# Lamp.net
KiCad netlist of a schematic drawn in EAGLE
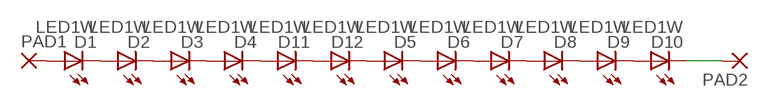
[diagram p0: schematic, sheet 1]

(export (version "E")
  (design (tool "Eeschema 10.0.6"))
  (components
    (comp (ref "D1")
      (value "LED1W")
      (footprint "eagle-import:LED-1W")
      (libsource (lib "eagle-import") (part "LED1W"))
    )
    (comp (ref "D2")
      (value "LED1W")
      (footprint "eagle-import:LED-1W")
      (libsource (lib "eagle-import") (part "LED1W"))
    )
    (comp (ref "D3")
      (value "LED1W")
      (footprint "eagle-import:LED-1W")
      (libsource (lib "eagle-import") (part "LED1W"))
    )
    (comp (ref "D4")
      (value "LED1W")
      (footprint "eagle-import:LED-1W")
      (libsource (lib "eagle-import") (part "LED1W"))
    )
    (comp (ref "D5")
      (value "LED1W")
      (footprint "eagle-import:LED-1W")
      (libsource (lib "eagle-import") (part "LED1W"))
    )
    (comp (ref "D6")
      (value "LED1W")
      (footprint "eagle-import:LED-1W")
      (libsource (lib "eagle-import") (part "LED1W"))
    )
    (comp (ref "D7")
      (value "LED1W")
      (footprint "eagle-import:LED-1W")
      (libsource (lib "eagle-import") (part "LED1W"))
    )
    (comp (ref "D8")
      (value "LED1W")
      (footprint "eagle-import:LED-1W")
      (libsource (lib "eagle-import") (part "LED1W"))
    )
    (comp (ref "D9")
      (value "LED1W")
      (footprint "eagle-import:LED-1W")
      (libsource (lib "eagle-import") (part "LED1W"))
    )
    (comp (ref "D10")
      (value "LED1W")
      (footprint "eagle-import:LED-1W")
      (libsource (lib "eagle-import") (part "LED1W"))
    )
    (comp (ref "D11")
      (value "LED1W")
      (footprint "eagle-import:LED-1W")
      (libsource (lib "eagle-import") (part "LED1W"))
    )
    (comp (ref "D12")
      (value "LED1W")
      (footprint "eagle-import:LED-1W")
      (libsource (lib "eagle-import") (part "LED1W"))
    )
    (comp (ref "PAD1")
      (value "3,81/1,4")
      (footprint "eagle-import:3,81_1,4")
      (libsource (lib "eagle-import") (part "3,81/1,4"))
    )
    (comp (ref "PAD2")
      (value "3,81/1,4")
      (footprint "eagle-import:3,81_1,4")
      (libsource (lib "eagle-import") (part "3,81/1,4"))
    )
  )
  (nets
    (net (code "1") (name "Net-(D1-C)") (class "Default")
      (node (ref "D1") (pin "K") (pinfunction "C_K") (pintype "passive"))
      (node (ref "D2") (pin "A") (pinfunction "A_A") (pintype "passive"))
    )
    (net (code "2") (name "Net-(D2-C)") (class "Default")
      (node (ref "D2") (pin "K") (pinfunction "C_K") (pintype "passive"))
      (node (ref "D3") (pin "A") (pinfunction "A_A") (pintype "passive"))
    )
    (net (code "3") (name "Net-(D3-C)") (class "Default")
      (node (ref "D3") (pin "K") (pinfunction "C_K") (pintype "passive"))
      (node (ref "D4") (pin "A") (pinfunction "A_A") (pintype "passive"))
    )
    (net (code "4") (name "Net-(D4-C)") (class "Default")
      (node (ref "D11") (pin "A") (pinfunction "A_A") (pintype "passive"))
      (node (ref "D4") (pin "K") (pinfunction "C_K") (pintype "passive"))
    )
    (net (code "5") (name "Net-(D5-C)") (class "Default")
      (node (ref "D5") (pin "K") (pinfunction "C_K") (pintype "passive"))
      (node (ref "D6") (pin "A") (pinfunction "A_A") (pintype "passive"))
    )
    (net (code "6") (name "Net-(D6-C)") (class "Default")
      (node (ref "D6") (pin "K") (pinfunction "C_K") (pintype "passive"))
      (node (ref "D7") (pin "A") (pinfunction "A_A") (pintype "passive"))
    )
    (net (code "7") (name "Net-(D7-C)") (class "Default")
      (node (ref "D7") (pin "K") (pinfunction "C_K") (pintype "passive"))
      (node (ref "D8") (pin "A") (pinfunction "A_A") (pintype "passive"))
    )
    (net (code "8") (name "Net-(D8-C)") (class "Default")
      (node (ref "D8") (pin "K") (pinfunction "C_K") (pintype "passive"))
      (node (ref "D9") (pin "A") (pinfunction "A_A") (pintype "passive"))
    )
    (net (code "9") (name "Net-(D9-C)") (class "Default")
      (node (ref "D10") (pin "A") (pinfunction "A_A") (pintype "passive"))
      (node (ref "D9") (pin "K") (pinfunction "C_K") (pintype "passive"))
    )
    (net (code "10") (name "Net-(D10-C)") (class "Default")
      (node (ref "D10") (pin "K") (pinfunction "C_K") (pintype "passive"))
      (node (ref "PAD2") (pin "1") (pinfunction "P_1") (pintype "passive"))
    )
    (net (code "11") (name "Net-(D11-C)") (class "Default")
      (node (ref "D11") (pin "K") (pinfunction "C_K") (pintype "passive"))
      (node (ref "D12") (pin "A") (pinfunction "A_A") (pintype "passive"))
    )
    (net (code "12") (name "Net-(D12-C)") (class "Default")
      (node (ref "D12") (pin "K") (pinfunction "C_K") (pintype "passive"))
      (node (ref "D5") (pin "A") (pinfunction "A_A") (pintype "passive"))
    )
    (net (code "13") (name "Net-(PAD1-P)") (class "Default")
      (node (ref "D1") (pin "A") (pinfunction "A_A") (pintype "passive"))
      (node (ref "PAD1") (pin "1") (pinfunction "P_1") (pintype "passive"))
    )
  )
)
